# Amp2.net
KiCad netlist of a schematic drawn in EasyEDA
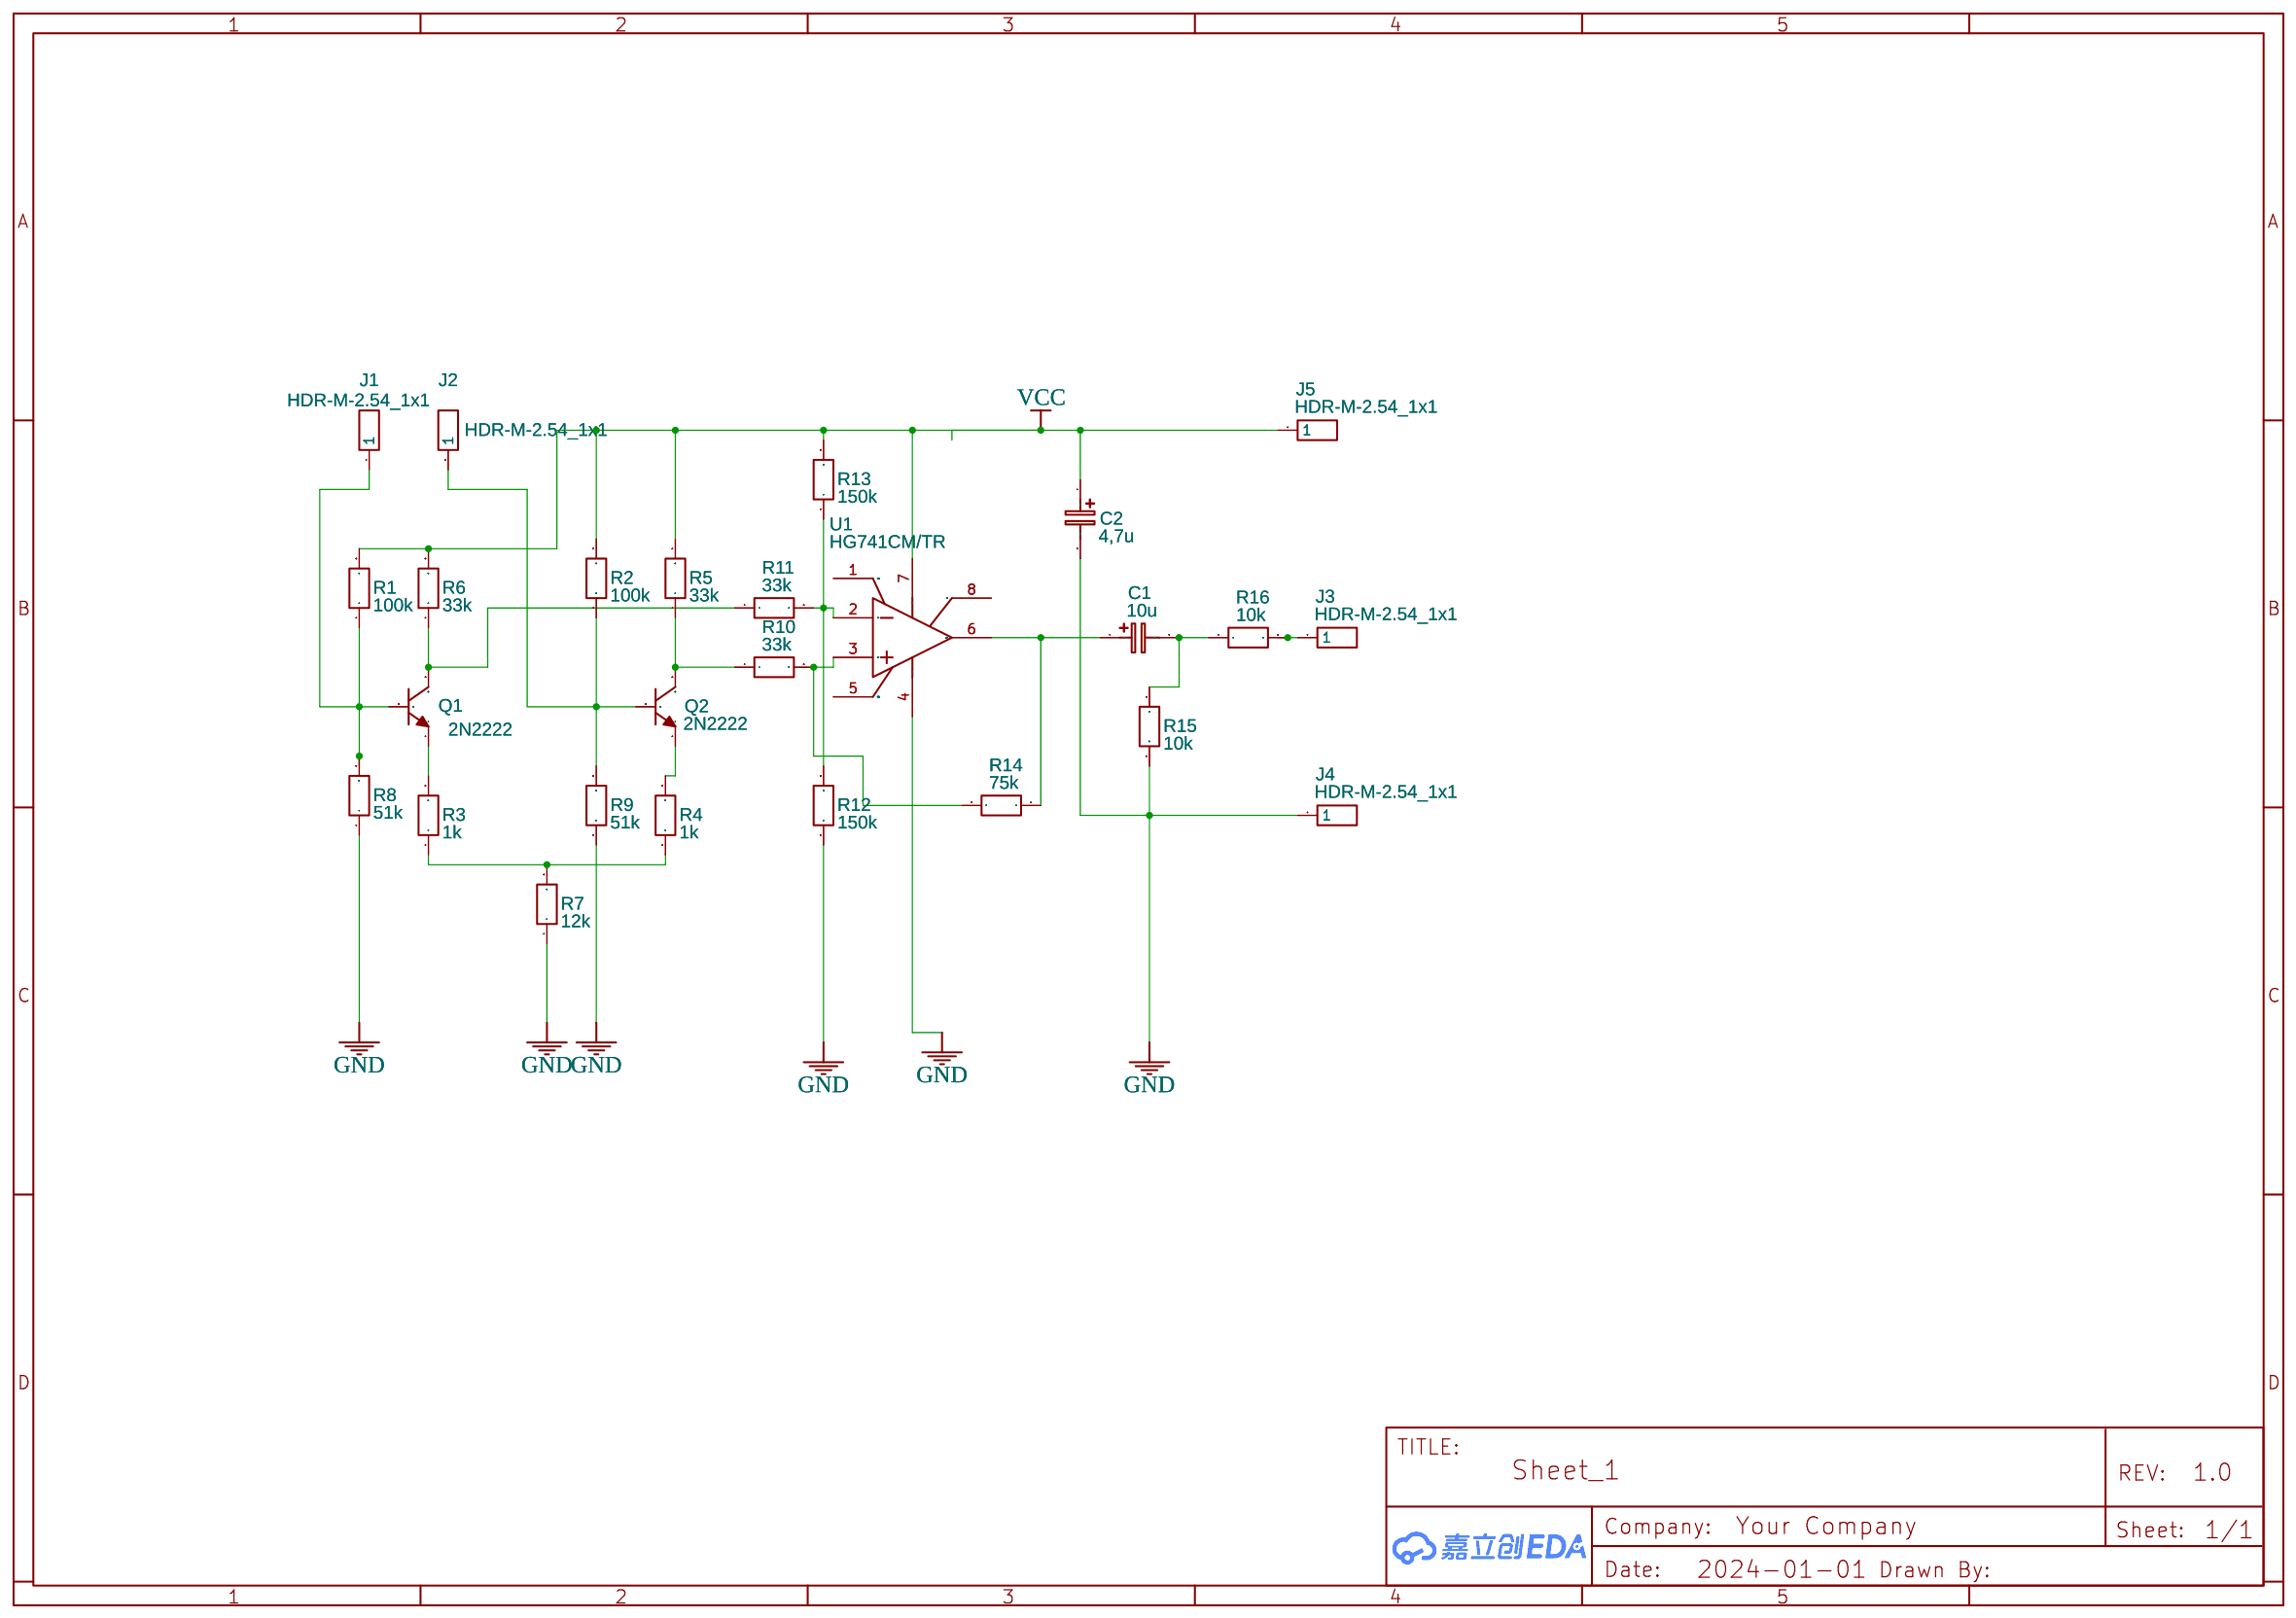
[diagram p0: schematic sheet]

(export (version "E")
  (design (tool "Eeschema 10.0.6"))
  (components
    (comp (ref "C1") (value "10u") (libsource (lib "") (part "C_Tan_SMD_A_EU_1")))
    (comp (ref "C2") (value "4,7u") (libsource (lib "") (part "C_Tan_SMD_A_EU")))
    (comp (ref "J1")
      (value "HDR-M-2.54_1x1")
      (fields (field (name "BOM_Supplier Part") "C81276"))
      (libsource (lib "") (part "HDR-M-2.54_1x1_1"))
    )
    (comp (ref "J2")
      (value "HDR-M-2.54_1x1")
      (fields (field (name "BOM_Supplier Part") "C81276"))
      (libsource (lib "") (part "HDR-M-2.54_1x1_1"))
    )
    (comp (ref "J3")
      (value "HDR-M-2.54_1x1")
      (fields (field (name "BOM_Supplier Part") "C81276"))
      (libsource (lib "") (part "HDR-M-2.54_1x1"))
    )
    (comp (ref "J4")
      (value "HDR-M-2.54_1x1")
      (fields (field (name "BOM_Supplier Part") "C81276"))
      (libsource (lib "") (part "HDR-M-2.54_1x1"))
    )
    (comp (ref "J5")
      (value "HDR-M-2.54_1x1")
      (fields (field (name "BOM_Supplier Part") "C81276"))
      (libsource (lib "") (part "HDR-M-2.54_1x1"))
    )
    (comp (ref "Q1")
      (value "2N2222")
      (fields
        (field (name "BOM_Manufacturer Part") "2n3904S-RTK/PS")
        (field (name "BOM_Supplier Part") "C18536")
      )
      (libsource (lib "") (part "2N3904(SOT-23)"))
    )
    (comp (ref "Q2")
      (value "2N2222")
      (fields
        (field (name "BOM_Manufacturer Part") "2n3904S-RTK/PS")
        (field (name "BOM_Supplier Part") "C18536")
      )
      (libsource (lib "") (part "2N3904(SOT-23)"))
    )
    (comp (ref "R1") (value "100k") (libsource (lib "") (part "R_0603_EU")))
    (comp (ref "R2") (value "100k") (libsource (lib "") (part "R_0603_EU")))
    (comp (ref "R3") (value "1k") (libsource (lib "") (part "R_0603_EU")))
    (comp (ref "R4") (value "1k") (libsource (lib "") (part "R_0603_EU")))
    (comp (ref "R5") (value "33k") (libsource (lib "") (part "R_0603_EU")))
    (comp (ref "R6") (value "33k") (libsource (lib "") (part "R_0603_EU")))
    (comp (ref "R7") (value "12k") (libsource (lib "") (part "R_0603_EU")))
    (comp (ref "R8") (value "51k") (libsource (lib "") (part "R_0603_EU")))
    (comp (ref "R9") (value "51k") (libsource (lib "") (part "R_0603_EU")))
    (comp (ref "R10") (value "33k") (libsource (lib "") (part "R_0603_EU_2")))
    (comp (ref "R11") (value "33k") (libsource (lib "") (part "R_0603_EU_2")))
    (comp (ref "R12") (value "150k") (libsource (lib "") (part "R_0603_EU")))
    (comp (ref "R13") (value "150k") (libsource (lib "") (part "R_0603_EU")))
    (comp (ref "R14") (value "75k") (libsource (lib "") (part "R_0603_EU_3")))
    (comp (ref "R15") (value "10k") (libsource (lib "") (part "R_0603_EU_1")))
    (comp (ref "R16") (value "10k") (libsource (lib "") (part "R_0603_EU_2")))
    (comp (ref "U1")
      (value "HG741CM/TR")
      (fields (field (name "Manufacturer") "HGSEMI(华冠)"))
      (libsource (lib "") (part "HG741CM/TR"))
    )
  )
  (nets
    (net (code "1") (name "GND") (class "Default")
      (node (ref "C2") (pin "2") (pinfunction "2_2") (pintype "unspecified"))
      (node (ref "J4") (pin "1") (pinfunction "1_1") (pintype "input"))
      (node (ref "R12") (pin "1") (pinfunction "1_1") (pintype "unspecified"))
      (node (ref "R15") (pin "2") (pinfunction "2_2") (pintype "unspecified"))
      (node (ref "R7") (pin "1") (pinfunction "1_1") (pintype "unspecified"))
      (node (ref "R8") (pin "1") (pinfunction "1_1") (pintype "unspecified"))
      (node (ref "R9") (pin "1") (pinfunction "1_1") (pintype "unspecified"))
      (node (ref "U1") (pin "4") (pinfunction "V-_4") (pintype "passive"))
    )
    (net (code "2") (name "Net-(C1-Pad2)") (class "Default")
      (node (ref "C1") (pin "2") (pinfunction "2_2") (pintype "unspecified"))
      (node (ref "R15") (pin "1") (pinfunction "1_1") (pintype "unspecified"))
      (node (ref "R16") (pin "1") (pinfunction "1_1") (pintype "unspecified"))
    )
    (net (code "3") (name "Net-(J3-Pad1)") (class "Default")
      (node (ref "J3") (pin "1") (pinfunction "1_1") (pintype "input"))
      (node (ref "R16") (pin "2") (pinfunction "2_2") (pintype "unspecified"))
    )
    (net (code "4") (name "Net-(Q1-B)") (class "Default")
      (node (ref "J1") (pin "1") (pinfunction "1_1") (pintype "input"))
      (node (ref "Q1") (pin "2") (pinfunction "B_2") (pintype "input"))
      (node (ref "R1") (pin "1") (pinfunction "1_1") (pintype "unspecified"))
      (node (ref "R8") (pin "2") (pinfunction "2_2") (pintype "unspecified"))
    )
    (net (code "5") (name "Net-(Q1-C)") (class "Default")
      (node (ref "Q1") (pin "3") (pinfunction "C_3") (pintype "input"))
      (node (ref "R11") (pin "1") (pinfunction "1_1") (pintype "unspecified"))
      (node (ref "R6") (pin "1") (pinfunction "1_1") (pintype "unspecified"))
    )
    (net (code "6") (name "Net-(Q1-E)") (class "Default")
      (node (ref "Q1") (pin "1") (pinfunction "E_1") (pintype "input"))
      (node (ref "R3") (pin "2") (pinfunction "2_2") (pintype "unspecified"))
    )
    (net (code "7") (name "Net-(Q2-B)") (class "Default")
      (node (ref "J2") (pin "1") (pinfunction "1_1") (pintype "input"))
      (node (ref "Q2") (pin "2") (pinfunction "B_2") (pintype "input"))
      (node (ref "R2") (pin "1") (pinfunction "1_1") (pintype "unspecified"))
      (node (ref "R9") (pin "2") (pinfunction "2_2") (pintype "unspecified"))
    )
    (net (code "8") (name "Net-(Q2-C)") (class "Default")
      (node (ref "Q2") (pin "3") (pinfunction "C_3") (pintype "input"))
      (node (ref "R10") (pin "1") (pinfunction "1_1") (pintype "unspecified"))
      (node (ref "R5") (pin "1") (pinfunction "1_1") (pintype "unspecified"))
    )
    (net (code "9") (name "Net-(Q2-E)") (class "Default")
      (node (ref "Q2") (pin "1") (pinfunction "E_1") (pintype "input"))
      (node (ref "R4") (pin "2") (pinfunction "2_2") (pintype "unspecified"))
    )
    (net (code "10") (name "Net-(R3-Pad1)") (class "Default")
      (node (ref "R3") (pin "1") (pinfunction "1_1") (pintype "unspecified"))
      (node (ref "R4") (pin "1") (pinfunction "1_1") (pintype "unspecified"))
      (node (ref "R7") (pin "2") (pinfunction "2_2") (pintype "unspecified"))
    )
    (net (code "11") (name "Net-(U1-+IN)") (class "Default")
      (node (ref "R10") (pin "2") (pinfunction "2_2") (pintype "unspecified"))
      (node (ref "R14") (pin "2") (pinfunction "2_2") (pintype "unspecified"))
      (node (ref "U1") (pin "3") (pinfunction "+IN_3") (pintype "unspecified"))
    )
    (net (code "12") (name "Net-(U1--IN)") (class "Default")
      (node (ref "R11") (pin "2") (pinfunction "2_2") (pintype "unspecified"))
      (node (ref "R12") (pin "2") (pinfunction "2_2") (pintype "unspecified"))
      (node (ref "R13") (pin "1") (pinfunction "1_1") (pintype "unspecified"))
      (node (ref "U1") (pin "2") (pinfunction "-IN_2") (pintype "unspecified"))
    )
    (net (code "13") (name "Net-(U1-OUTPUT)") (class "Default")
      (node (ref "C1") (pin "1") (pinfunction "1_1") (pintype "unspecified"))
      (node (ref "R14") (pin "1") (pinfunction "1_1") (pintype "unspecified"))
      (node (ref "U1") (pin "6") (pinfunction "OUTPUT_6") (pintype "unspecified"))
    )
    (net (code "14") (name "VCC") (class "Default")
      (node (ref "C2") (pin "1") (pinfunction "1_1") (pintype "unspecified"))
      (node (ref "J5") (pin "1") (pinfunction "1_1") (pintype "input"))
      (node (ref "R1") (pin "2") (pinfunction "2_2") (pintype "unspecified"))
      (node (ref "R13") (pin "2") (pinfunction "2_2") (pintype "unspecified"))
      (node (ref "R2") (pin "2") (pinfunction "2_2") (pintype "unspecified"))
      (node (ref "R5") (pin "2") (pinfunction "2_2") (pintype "unspecified"))
      (node (ref "R6") (pin "2") (pinfunction "2_2") (pintype "unspecified"))
      (node (ref "U1") (pin "7") (pinfunction "V+_7") (pintype "passive"))
    )
    (net (code "15") (name "unconnected-(U1-NC-Pad8)") (class "Default")
      (node (ref "U1") (pin "8") (pinfunction "NC_8") (pintype "unspecified"))
    )
    (net (code "16") (name "unconnected-(U1-OFFSET_NULL-Pad1)") (class "Default")
      (node (ref "U1") (pin "1") (pinfunction "OFFSET_NULL_1") (pintype "unspecified"))
    )
    (net (code "17") (name "unconnected-(U1-OFFSET_NULL-Pad5)") (class "Default")
      (node (ref "U1") (pin "5") (pinfunction "OFFSET_NULL_5") (pintype "unspecified"))
    )
  )
)
